# riscurino.net
KiCad netlist of a schematic drawn in EAGLE
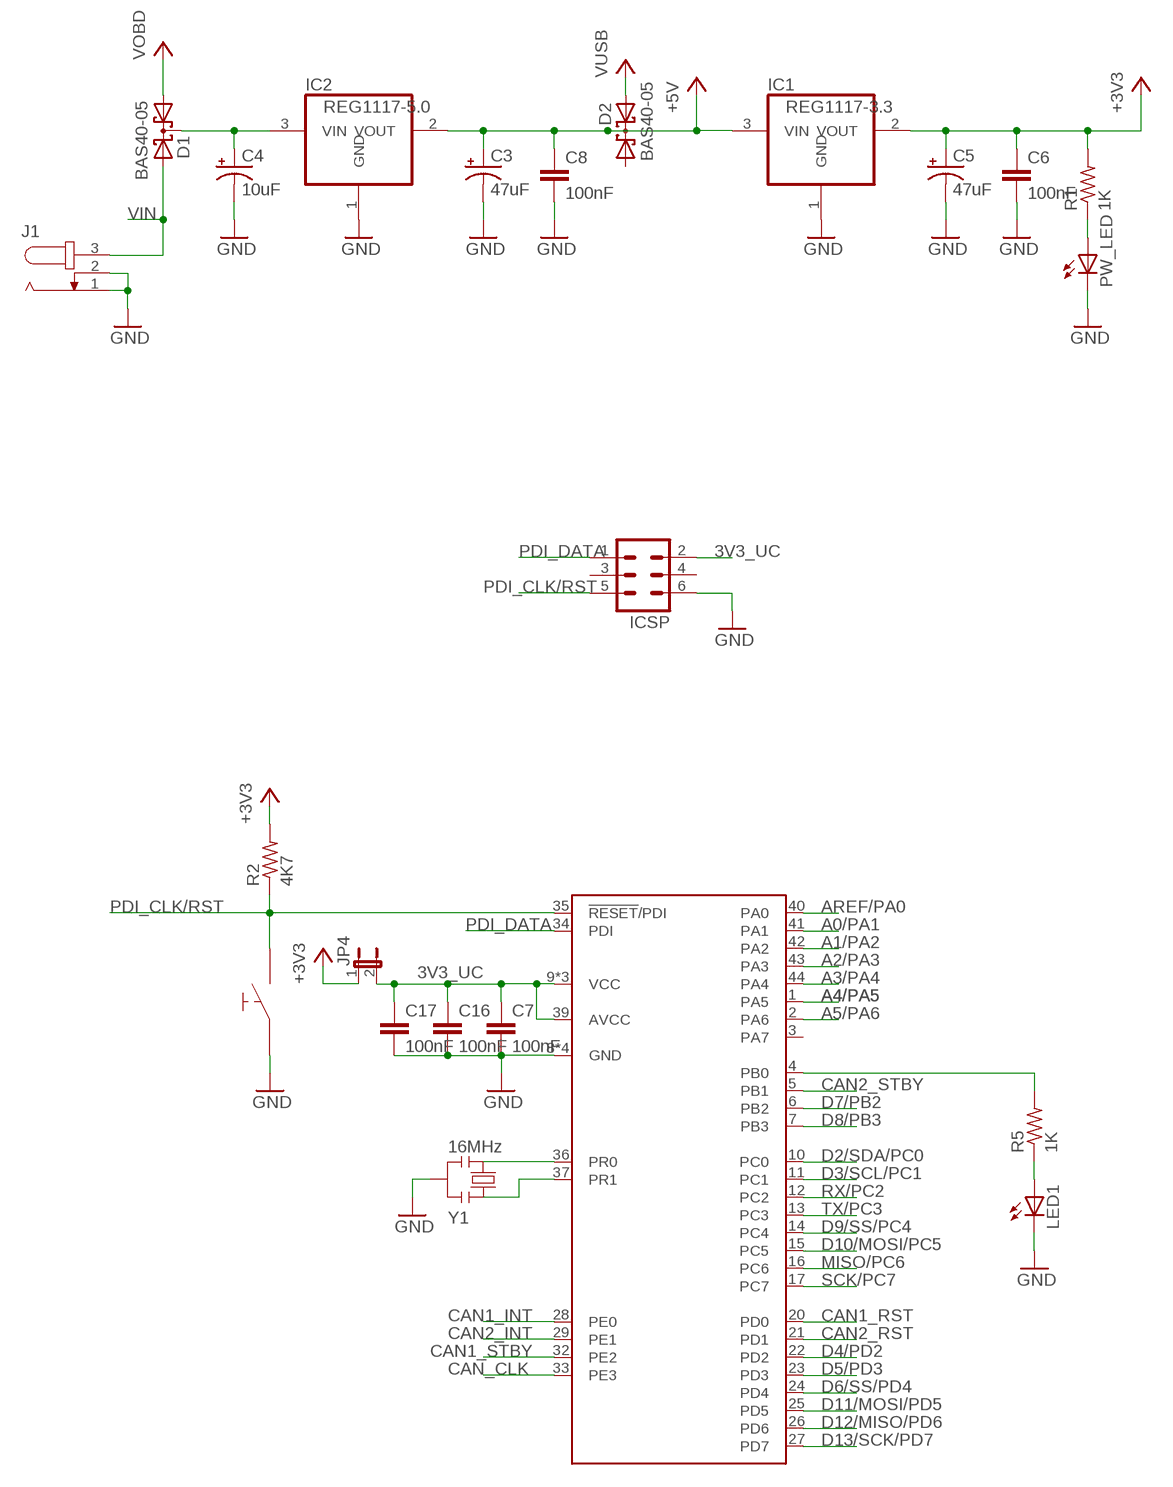
[diagram p0: schematic, sheet 1, part 1 of 2]
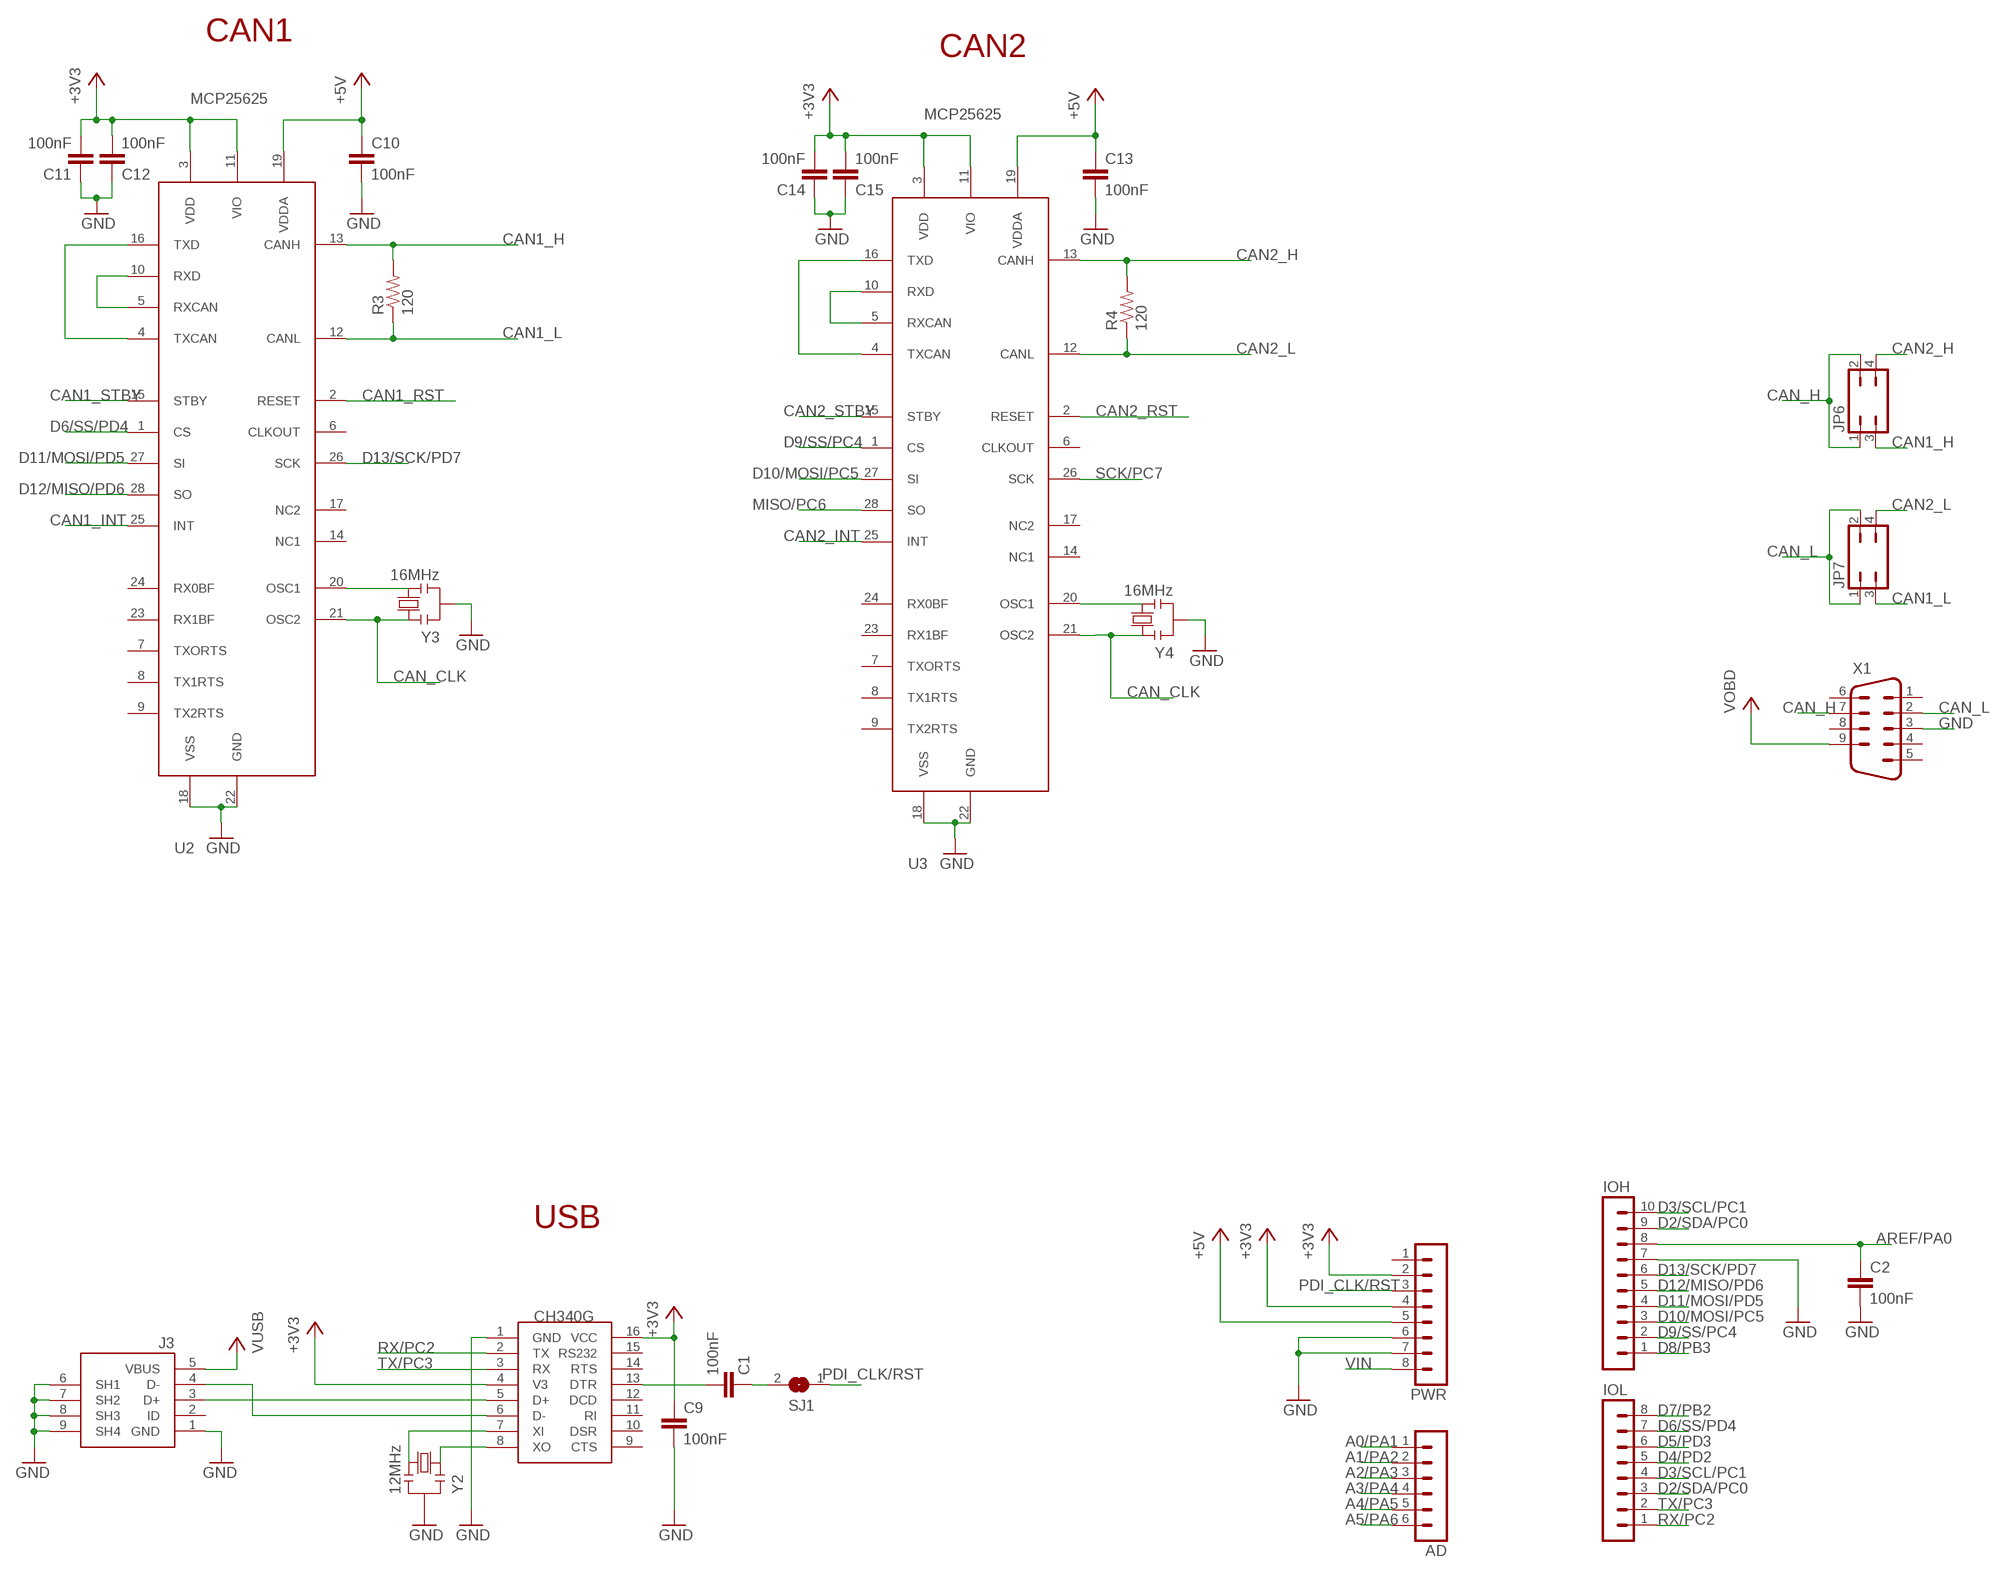
[diagram p1: schematic, sheet 1, part 2 of 2]

(export (version "E")
  (design (tool "Eeschema 10.0.6"))
  (components
    (comp (ref "AD")
      (value "MA06-1")
      (footprint "eagle-import:MA06-1")
      (libsource (lib "eagle-import") (part "MA06-1"))
    )
    (comp (ref "C1")
      (value "100nF")
      (footprint "eagle-import:C0805")
      (libsource (lib "eagle-import") (part "C-EUC0805"))
    )
    (comp (ref "C2")
      (value "100nF")
      (footprint "eagle-import:C0805")
      (libsource (lib "eagle-import") (part "C-EUC0805"))
    )
    (comp (ref "C3")
      (value "47uF")
      (footprint "eagle-import:PANASONIC_C")
      (libsource (lib "eagle-import") (part "CPOL-USC"))
    )
    (comp (ref "C4")
      (value "10uF")
      (footprint "eagle-import:PANASONIC_C")
      (libsource (lib "eagle-import") (part "CPOL-USC"))
    )
    (comp (ref "C5")
      (value "47uF")
      (footprint "eagle-import:PANASONIC_C")
      (libsource (lib "eagle-import") (part "CPOL-USC"))
    )
    (comp (ref "C6")
      (value "100nF")
      (footprint "eagle-import:C0805")
      (libsource (lib "eagle-import") (part "C-EUC0805"))
    )
    (comp (ref "C7")
      (value "100nF")
      (footprint "eagle-import:C0805")
      (libsource (lib "eagle-import") (part "C-EUC0805"))
    )
    (comp (ref "C8")
      (value "100nF")
      (footprint "eagle-import:C0805")
      (libsource (lib "eagle-import") (part "C-EUC0805"))
    )
    (comp (ref "C9")
      (value "100nF")
      (footprint "eagle-import:C0805")
      (libsource (lib "eagle-import") (part "C-EUC0805"))
    )
    (comp (ref "C10")
      (value "100nF")
      (footprint "eagle-import:C0805")
      (libsource (lib "eagle-import") (part "C-EUC0805"))
    )
    (comp (ref "C11")
      (value "100nF")
      (footprint "eagle-import:C0805")
      (libsource (lib "eagle-import") (part "C-EUC0805"))
    )
    (comp (ref "C12")
      (value "100nF")
      (footprint "eagle-import:C0805")
      (libsource (lib "eagle-import") (part "C-EUC0805"))
    )
    (comp (ref "C13")
      (value "100nF")
      (footprint "eagle-import:C0805")
      (libsource (lib "eagle-import") (part "C-EUC0805"))
    )
    (comp (ref "C14")
      (value "100nF")
      (footprint "eagle-import:C0805")
      (libsource (lib "eagle-import") (part "C-EUC0805"))
    )
    (comp (ref "C15")
      (value "100nF")
      (footprint "eagle-import:C0805")
      (libsource (lib "eagle-import") (part "C-EUC0805"))
    )
    (comp (ref "C16")
      (value "100nF")
      (footprint "eagle-import:C0805")
      (libsource (lib "eagle-import") (part "C-EUC0805"))
    )
    (comp (ref "C17")
      (value "100nF")
      (footprint "eagle-import:C0805")
      (libsource (lib "eagle-import") (part "C-EUC0805"))
    )
    (comp (ref "D1")
      (value "BAS40-05")
      (footprint "eagle-import:SOT23")
      (libsource (lib "eagle-import") (part "BAS40-05"))
    )
    (comp (ref "D2")
      (value "BAS40-05")
      (footprint "eagle-import:SOT23")
      (libsource (lib "eagle-import") (part "BAS40-05"))
    )
    (comp (ref "IC1")
      (value "REG1117-3.3")
      (footprint "eagle-import:SOT223")
      (fields (field (name "MPN") "REG1117"))
      (libsource (lib "eagle-import") (part "REG1117"))
    )
    (comp (ref "IC2")
      (value "REG1117-5.0")
      (footprint "eagle-import:SOT223")
      (fields (field (name "MPN") "REG1117"))
      (libsource (lib "eagle-import") (part "REG1117"))
    )
    (comp (ref "ICSP")
      (value "MA03-2")
      (footprint "eagle-import:MA03-2")
      (libsource (lib "eagle-import") (part "MA03-2"))
    )
    (comp (ref "IOH")
      (value "MA10-1")
      (footprint "eagle-import:MA10-1")
      (libsource (lib "eagle-import") (part "MA10-1"))
    )
    (comp (ref "IOL")
      (value "MA08-1")
      (footprint "eagle-import:MA08-1")
      (libsource (lib "eagle-import") (part "MA08-1"))
    )
    (comp (ref "J1")
      (value "JACK-PLUG0")
      (footprint "eagle-import:SPC4077")
      (libsource (lib "eagle-import") (part "JACK-PLUG0"))
    )
    (comp (ref "J3")
      (value "0219_14850")
      (footprint "eagle-import:USB-MINI-B_2")
      (fields (field (name "PART_NUMBER") "14850"))
      (libsource (lib "eagle-import") (part "0219_14850"))
    )
    (comp (ref "JP4")
      (value "JP1E")
      (footprint "eagle-import:JP1")
      (libsource (lib "eagle-import") (part "JP1E"))
    )
    (comp (ref "JP6")
      (value "JP2Q")
      (footprint "eagle-import:JP2Q")
      (libsource (lib "eagle-import") (part "JP2Q"))
    )
    (comp (ref "JP7")
      (value "JP2Q")
      (footprint "eagle-import:JP2Q")
      (libsource (lib "eagle-import") (part "JP2Q"))
    )
    (comp (ref "LED1")
      (value "LEDCHIPLED_0805")
      (footprint "eagle-import:CHIPLED_0805")
      (libsource (lib "eagle-import") (part "LEDCHIPLED_0805"))
    )
    (comp (ref "PWR")
      (value "MA08-1")
      (footprint "eagle-import:MA08-1")
      (libsource (lib "eagle-import") (part "MA08-1"))
    )
    (comp (ref "PW_LED")
      (value "LEDCHIPLED_0805")
      (footprint "eagle-import:CHIPLED_0805")
      (libsource (lib "eagle-import") (part "LEDCHIPLED_0805"))
    )
    (comp (ref "R1")
      (value "1K")
      (footprint "eagle-import:R0805")
      (libsource (lib "eagle-import") (part "R-US_R0805"))
    )
    (comp (ref "R2")
      (value "4K7")
      (footprint "eagle-import:R0805")
      (libsource (lib "eagle-import") (part "R-US_R0805"))
    )
    (comp (ref "R3")
      (value "120")
      (footprint "eagle-import:R0805")
      (libsource (lib "eagle-import") (part "R-US_R0805"))
    )
    (comp (ref "R4")
      (value "120")
      (footprint "eagle-import:R0805")
      (libsource (lib "eagle-import") (part "R-US_R0805"))
    )
    (comp (ref "R5")
      (value "1K")
      (footprint "eagle-import:R0805")
      (libsource (lib "eagle-import") (part "R-US_R0805"))
    )
    (comp (ref "SJ1") (value "SJ") (footprint "eagle-import:SJ") (libsource (lib "eagle-import") (part "SJ")))
    (comp (ref "U$1")
      (value "SWITCH_3X6")
      (footprint "eagle-import:SWITCH_3X6")
      (libsource (lib "eagle-import") (part "SWITCH_3X6"))
    )
    (comp (ref "U1")
      (value "ATXMEGA128A4U-AU")
      (footprint "eagle-import:TQFP-44A-44")
      (libsource (lib "eagle-import") (part "ATXMEGA128A4U-AU"))
    )
    (comp (ref "U2")
      (value "MCP25625")
      (footprint "eagle-import:QFN28")
      (libsource (lib "eagle-import") (part "MCP25625"))
    )
    (comp (ref "U3")
      (value "MCP25625")
      (footprint "eagle-import:QFN28")
      (libsource (lib "eagle-import") (part "MCP25625"))
    )
    (comp (ref "U4")
      (value "CH340G")
      (footprint "eagle-import:SOIC16")
      (libsource (lib "eagle-import") (part "CH340G"))
    )
    (comp (ref "X1")
      (value "M09HP")
      (footprint "eagle-import:M09HP")
      (libsource (lib "eagle-import") (part "M09HP"))
    )
    (comp (ref "Y1")
      (value "16MHz")
      (footprint "eagle-import:RESONATOR")
      (fields (field (name "PART_NUMBER") "CSTCE16M0V53-R0"))
      (libsource (lib "eagle-import") (part "0011_CSTCE16M0V53-R0"))
    )
    (comp (ref "Y2")
      (value "12MHz")
      (footprint "eagle-import:RESONATOR")
      (fields (field (name "PART_NUMBER") "CSTCE16M0V53-R0"))
      (libsource (lib "eagle-import") (part "0011_CSTCE16M0V53-R0"))
    )
    (comp (ref "Y3")
      (value "16MHz")
      (footprint "eagle-import:RESONATOR")
      (fields (field (name "PART_NUMBER") "CSTCE16M0V53-R0"))
      (libsource (lib "eagle-import") (part "0011_CSTCE16M0V53-R0"))
    )
    (comp (ref "Y4")
      (value "16MHz")
      (footprint "eagle-import:RESONATOR")
      (fields (field (name "PART_NUMBER") "CSTCE16M0V53-R0"))
      (libsource (lib "eagle-import") (part "0011_CSTCE16M0V53-R0"))
    )
  )
  (nets
    (net (code "1") (name "+3V3") (class "Default")
      (node (ref "C11") (pin "2") (pinfunction "2_2") (pintype "passive"))
      (node (ref "C12") (pin "2") (pinfunction "2_2") (pintype "passive"))
      (node (ref "C14") (pin "2") (pinfunction "2_2") (pintype "passive"))
      (node (ref "C15") (pin "2") (pinfunction "2_2") (pintype "passive"))
      (node (ref "C5") (pin "+") (pinfunction "+_+") (pintype "passive"))
      (node (ref "C6") (pin "1") (pinfunction "1_1") (pintype "passive"))
      (node (ref "C9") (pin "1") (pinfunction "1_1") (pintype "passive"))
      (node (ref "IC1") (pin "2") (pinfunction "VOUT_2") (pintype "output"))
      (node (ref "JP4") (pin "1") (pinfunction "1_1") (pintype "passive"))
      (node (ref "PWR") (pin "2") (pinfunction "2_2") (pintype "passive"))
      (node (ref "PWR") (pin "4") (pinfunction "4_4") (pintype "passive"))
      (node (ref "R1") (pin "2") (pinfunction "2_2") (pintype "passive"))
      (node (ref "R2") (pin "2") (pinfunction "2_2") (pintype "passive"))
      (node (ref "U2") (pin "11") (pinfunction "VIO_11") (pintype "bidirectional"))
      (node (ref "U2") (pin "3") (pinfunction "VDD_3") (pintype "power_in"))
      (node (ref "U3") (pin "11") (pinfunction "VIO_11") (pintype "bidirectional"))
      (node (ref "U3") (pin "3") (pinfunction "VDD_3") (pintype "power_in"))
      (node (ref "U4") (pin "16") (pinfunction "VCC_16") (pintype "bidirectional"))
      (node (ref "U4") (pin "4") (pinfunction "V3_4") (pintype "bidirectional"))
    )
    (net (code "2") (name "+5V") (class "Default")
      (node (ref "C10") (pin "1") (pinfunction "1_1") (pintype "passive"))
      (node (ref "C13") (pin "1") (pinfunction "1_1") (pintype "passive"))
      (node (ref "C3") (pin "+") (pinfunction "+_+") (pintype "passive"))
      (node (ref "C8") (pin "1") (pinfunction "1_1") (pintype "passive"))
      (node (ref "D2") (pin "3") (pinfunction "C_3") (pintype "passive"))
      (node (ref "IC1") (pin "3") (pinfunction "VIN_3") (pintype "input"))
      (node (ref "IC2") (pin "2") (pinfunction "VOUT_2") (pintype "output"))
      (node (ref "PWR") (pin "5") (pinfunction "5_5") (pintype "passive"))
      (node (ref "U2") (pin "19") (pinfunction "VDDA_19") (pintype "power_in"))
      (node (ref "U3") (pin "19") (pinfunction "VDDA_19") (pintype "power_in"))
    )
    (net (code "3") (name "/3V3_UC") (class "Default")
      (node (ref "C16") (pin "1") (pinfunction "1_1") (pintype "passive"))
      (node (ref "C17") (pin "1") (pinfunction "1_1") (pintype "passive"))
      (node (ref "C7") (pin "1") (pinfunction "1_1") (pintype "passive"))
      (node (ref "ICSP") (pin "2") (pinfunction "2_2") (pintype "passive"))
      (node (ref "JP4") (pin "2") (pinfunction "2_2") (pintype "passive"))
      (node (ref "U1") (pin "19") (pinfunction "VCC_19") (pintype "power_in"))
      (node (ref "U1") (pin "31") (pinfunction "VCC_31") (pintype "power_in"))
      (node (ref "U1") (pin "39") (pinfunction "AVCC_39") (pintype "power_in"))
      (node (ref "U1") (pin "9") (pinfunction "VCC_9") (pintype "power_in"))
    )
    (net (code "4") (name "/A0{slash}PA1") (class "Default")
      (node (ref "AD") (pin "1") (pinfunction "1_1") (pintype "passive"))
      (node (ref "U1") (pin "41") (pinfunction "PA1_41") (pintype "bidirectional"))
    )
    (net (code "5") (name "/A1{slash}PA2") (class "Default")
      (node (ref "AD") (pin "2") (pinfunction "2_2") (pintype "passive"))
      (node (ref "U1") (pin "42") (pinfunction "PA2_42") (pintype "bidirectional"))
    )
    (net (code "6") (name "/A2{slash}PA3") (class "Default")
      (node (ref "AD") (pin "3") (pinfunction "3_3") (pintype "passive"))
      (node (ref "U1") (pin "43") (pinfunction "PA3_43") (pintype "bidirectional"))
    )
    (net (code "7") (name "/A3{slash}PA4") (class "Default")
      (node (ref "AD") (pin "4") (pinfunction "4_4") (pintype "passive"))
      (node (ref "U1") (pin "44") (pinfunction "PA4_44") (pintype "bidirectional"))
    )
    (net (code "8") (name "/A4{slash}PA5") (class "Default")
      (node (ref "AD") (pin "5") (pinfunction "5_5") (pintype "passive"))
      (node (ref "U1") (pin "1") (pinfunction "PA5_1") (pintype "bidirectional"))
    )
    (net (code "9") (name "/A5{slash}PA6") (class "Default")
      (node (ref "AD") (pin "6") (pinfunction "6_6") (pintype "passive"))
      (node (ref "U1") (pin "2") (pinfunction "PA6_2") (pintype "bidirectional"))
    )
    (net (code "10") (name "/AREF{slash}PA0") (class "Default")
      (node (ref "C2") (pin "1") (pinfunction "1_1") (pintype "passive"))
      (node (ref "IOH") (pin "8") (pinfunction "8_8") (pintype "passive"))
      (node (ref "U1") (pin "40") (pinfunction "PA0_40") (pintype "bidirectional"))
    )
    (net (code "11") (name "/CAN1_H") (class "Default")
      (node (ref "JP6") (pin "3") (pinfunction "3_3") (pintype "passive"))
      (node (ref "R3") (pin "2") (pinfunction "2_2") (pintype "passive"))
      (node (ref "U2") (pin "13") (pinfunction "CANH_13") (pintype "bidirectional"))
    )
    (net (code "12") (name "/CAN1_INT") (class "Default")
      (node (ref "U1") (pin "28") (pinfunction "PE0_28") (pintype "bidirectional"))
      (node (ref "U2") (pin "25") (pinfunction "INT_25") (pintype "bidirectional"))
    )
    (net (code "13") (name "/CAN1_L") (class "Default")
      (node (ref "JP7") (pin "3") (pinfunction "3_3") (pintype "passive"))
      (node (ref "R3") (pin "1") (pinfunction "1_1") (pintype "passive"))
      (node (ref "U2") (pin "12") (pinfunction "CANL_12") (pintype "bidirectional"))
    )
    (net (code "14") (name "/CAN1_RST") (class "Default")
      (node (ref "U1") (pin "20") (pinfunction "PD0_20") (pintype "bidirectional"))
      (node (ref "U2") (pin "2") (pinfunction "RESET_2") (pintype "bidirectional"))
    )
    (net (code "15") (name "/CAN1_STBY") (class "Default")
      (node (ref "U1") (pin "32") (pinfunction "PE2_32") (pintype "bidirectional"))
      (node (ref "U2") (pin "15") (pinfunction "STBY_15") (pintype "bidirectional"))
    )
    (net (code "16") (name "/CAN2_H") (class "Default")
      (node (ref "JP6") (pin "4") (pinfunction "4_4") (pintype "passive"))
      (node (ref "R4") (pin "2") (pinfunction "2_2") (pintype "passive"))
      (node (ref "U3") (pin "13") (pinfunction "CANH_13") (pintype "bidirectional"))
    )
    (net (code "17") (name "/CAN2_INT") (class "Default")
      (node (ref "U1") (pin "29") (pinfunction "PE1_29") (pintype "bidirectional"))
      (node (ref "U3") (pin "25") (pinfunction "INT_25") (pintype "bidirectional"))
    )
    (net (code "18") (name "/CAN2_L") (class "Default")
      (node (ref "JP7") (pin "4") (pinfunction "4_4") (pintype "passive"))
      (node (ref "R4") (pin "1") (pinfunction "1_1") (pintype "passive"))
      (node (ref "U3") (pin "12") (pinfunction "CANL_12") (pintype "bidirectional"))
    )
    (net (code "19") (name "/CAN2_RST") (class "Default")
      (node (ref "U1") (pin "21") (pinfunction "PD1_21") (pintype "bidirectional"))
      (node (ref "U3") (pin "2") (pinfunction "RESET_2") (pintype "bidirectional"))
    )
    (net (code "20") (name "/CAN2_STBY") (class "Default")
      (node (ref "U1") (pin "5") (pinfunction "PB1_5") (pintype "bidirectional"))
      (node (ref "U3") (pin "15") (pinfunction "STBY_15") (pintype "bidirectional"))
    )
    (net (code "21") (name "/CAN_CLK") (class "Default")
      (node (ref "U1") (pin "33") (pinfunction "PE3_33") (pintype "bidirectional"))
      (node (ref "U2") (pin "21") (pinfunction "OSC2_21") (pintype "bidirectional"))
      (node (ref "U3") (pin "21") (pinfunction "OSC2_21") (pintype "bidirectional"))
      (node (ref "Y3") (pin "1") (pinfunction "1_1") (pintype "passive"))
      (node (ref "Y4") (pin "1") (pinfunction "1_1") (pintype "passive"))
    )
    (net (code "22") (name "/CAN_H") (class "Default")
      (node (ref "JP6") (pin "1") (pinfunction "1_1") (pintype "passive"))
      (node (ref "JP6") (pin "2") (pinfunction "2_2") (pintype "passive"))
      (node (ref "X1") (pin "7") (pinfunction "7_7") (pintype "passive"))
    )
    (net (code "23") (name "/CAN_L") (class "Default")
      (node (ref "JP7") (pin "1") (pinfunction "1_1") (pintype "passive"))
      (node (ref "JP7") (pin "2") (pinfunction "2_2") (pintype "passive"))
      (node (ref "X1") (pin "2") (pinfunction "2_2") (pintype "passive"))
    )
    (net (code "24") (name "/D2{slash}SDA{slash}PC0") (class "Default")
      (node (ref "IOH") (pin "9") (pinfunction "9_9") (pintype "passive"))
      (node (ref "IOL") (pin "3") (pinfunction "3_3") (pintype "passive"))
      (node (ref "U1") (pin "10") (pinfunction "PC0_10") (pintype "bidirectional"))
    )
    (net (code "25") (name "/D3{slash}SCL{slash}PC1") (class "Default")
      (node (ref "IOH") (pin "10") (pinfunction "10_10") (pintype "passive"))
      (node (ref "IOL") (pin "4") (pinfunction "4_4") (pintype "passive"))
      (node (ref "U1") (pin "11") (pinfunction "PC1_11") (pintype "bidirectional"))
    )
    (net (code "26") (name "/D4{slash}PD2") (class "Default")
      (node (ref "IOL") (pin "5") (pinfunction "5_5") (pintype "passive"))
      (node (ref "U1") (pin "22") (pinfunction "PD2_22") (pintype "bidirectional"))
    )
    (net (code "27") (name "/D5{slash}PD3") (class "Default")
      (node (ref "IOL") (pin "6") (pinfunction "6_6") (pintype "passive"))
      (node (ref "U1") (pin "23") (pinfunction "PD3_23") (pintype "bidirectional"))
    )
    (net (code "28") (name "/D6{slash}SS{slash}PD4") (class "Default")
      (node (ref "IOL") (pin "7") (pinfunction "7_7") (pintype "passive"))
      (node (ref "U1") (pin "24") (pinfunction "PD4_24") (pintype "bidirectional"))
      (node (ref "U2") (pin "1") (pinfunction "CS_1") (pintype "bidirectional"))
    )
    (net (code "29") (name "/D7{slash}PB2") (class "Default")
      (node (ref "IOL") (pin "8") (pinfunction "8_8") (pintype "passive"))
      (node (ref "U1") (pin "6") (pinfunction "PB2_6") (pintype "bidirectional"))
    )
    (net (code "30") (name "/D8{slash}PB3") (class "Default")
      (node (ref "IOH") (pin "1") (pinfunction "1_1") (pintype "passive"))
      (node (ref "U1") (pin "7") (pinfunction "PB3_7") (pintype "bidirectional"))
    )
    (net (code "31") (name "/D9{slash}SS{slash}PC4") (class "Default")
      (node (ref "IOH") (pin "2") (pinfunction "2_2") (pintype "passive"))
      (node (ref "U1") (pin "14") (pinfunction "PC4_14") (pintype "bidirectional"))
      (node (ref "U3") (pin "1") (pinfunction "CS_1") (pintype "bidirectional"))
    )
    (net (code "32") (name "/D10{slash}MOSI{slash}PC5") (class "Default")
      (node (ref "IOH") (pin "3") (pinfunction "3_3") (pintype "passive"))
      (node (ref "U1") (pin "15") (pinfunction "PC5_15") (pintype "bidirectional"))
      (node (ref "U3") (pin "27") (pinfunction "SI_27") (pintype "bidirectional"))
    )
    (net (code "33") (name "/D11{slash}MOSI{slash}PD5") (class "Default")
      (node (ref "IOH") (pin "4") (pinfunction "4_4") (pintype "passive"))
      (node (ref "U1") (pin "25") (pinfunction "PD5_25") (pintype "bidirectional"))
      (node (ref "U2") (pin "27") (pinfunction "SI_27") (pintype "bidirectional"))
    )
    (net (code "34") (name "/D12{slash}MISO{slash}PD6") (class "Default")
      (node (ref "IOH") (pin "5") (pinfunction "5_5") (pintype "passive"))
      (node (ref "U1") (pin "26") (pinfunction "PD6_26") (pintype "bidirectional"))
      (node (ref "U2") (pin "28") (pinfunction "SO_28") (pintype "bidirectional"))
    )
    (net (code "35") (name "/D13{slash}SCK{slash}PD7") (class "Default")
      (node (ref "IOH") (pin "6") (pinfunction "6_6") (pintype "passive"))
      (node (ref "U1") (pin "27") (pinfunction "PD7_27") (pintype "bidirectional"))
      (node (ref "U2") (pin "26") (pinfunction "SCK_26") (pintype "bidirectional"))
    )
    (net (code "36") (name "/MISO{slash}PC6") (class "Default")
      (node (ref "U1") (pin "16") (pinfunction "PC6_16") (pintype "bidirectional"))
      (node (ref "U3") (pin "28") (pinfunction "SO_28") (pintype "bidirectional"))
    )
    (net (code "37") (name "/PDI_CLK{slash}RST") (class "Default")
      (node (ref "ICSP") (pin "5") (pinfunction "5_5") (pintype "passive"))
      (node (ref "PWR") (pin "3") (pinfunction "3_3") (pintype "passive"))
      (node (ref "R2") (pin "1") (pinfunction "1_1") (pintype "passive"))
      (node (ref "SJ1") (pin "1") (pinfunction "1_1") (pintype "passive"))
      (node (ref "U$1") (pin "P$2") (pinfunction "P$2_P$2") (pintype "bidirectional"))
      (node (ref "U1") (pin "35") (pinfunction "~{RESET}/PDI_35") (pintype "bidirectional"))
    )
    (net (code "38") (name "/PDI_DATA") (class "Default")
      (node (ref "ICSP") (pin "1") (pinfunction "1_1") (pintype "passive"))
      (node (ref "U1") (pin "34") (pinfunction "PDI_34") (pintype "bidirectional"))
    )
    (net (code "39") (name "/RX{slash}PC2") (class "Default")
      (node (ref "IOL") (pin "1") (pinfunction "1_1") (pintype "passive"))
      (node (ref "U1") (pin "12") (pinfunction "PC2_12") (pintype "bidirectional"))
      (node (ref "U4") (pin "2") (pinfunction "TX_2") (pintype "bidirectional"))
    )
    (net (code "40") (name "/SCK{slash}PC7") (class "Default")
      (node (ref "U1") (pin "17") (pinfunction "PC7_17") (pintype "bidirectional"))
      (node (ref "U3") (pin "26") (pinfunction "SCK_26") (pintype "bidirectional"))
    )
    (net (code "41") (name "/TX{slash}PC3") (class "Default")
      (node (ref "IOL") (pin "2") (pinfunction "2_2") (pintype "passive"))
      (node (ref "U1") (pin "13") (pinfunction "PC3_13") (pintype "bidirectional"))
      (node (ref "U4") (pin "3") (pinfunction "RX_3") (pintype "bidirectional"))
    )
    (net (code "42") (name "/VIN") (class "Default")
      (node (ref "D1") (pin "2") (pinfunction "A2_2") (pintype "passive"))
      (node (ref "J1") (pin "3") (pinfunction "3_3") (pintype "passive"))
      (node (ref "PWR") (pin "8") (pinfunction "8_8") (pintype "passive"))
    )
    (net (code "43") (name "GND") (class "Default")
      (node (ref "C10") (pin "2") (pinfunction "2_2") (pintype "passive"))
      (node (ref "C11") (pin "1") (pinfunction "1_1") (pintype "passive"))
      (node (ref "C12") (pin "1") (pinfunction "1_1") (pintype "passive"))
      (node (ref "C13") (pin "2") (pinfunction "2_2") (pintype "passive"))
      (node (ref "C14") (pin "1") (pinfunction "1_1") (pintype "passive"))
      (node (ref "C15") (pin "1") (pinfunction "1_1") (pintype "passive"))
      (node (ref "C16") (pin "2") (pinfunction "2_2") (pintype "passive"))
      (node (ref "C17") (pin "2") (pinfunction "2_2") (pintype "passive"))
      (node (ref "C2") (pin "2") (pinfunction "2_2") (pintype "passive"))
      (node (ref "C3") (pin "-") (pinfunction "-_-") (pintype "passive"))
      (node (ref "C4") (pin "-") (pinfunction "-_-") (pintype "passive"))
      (node (ref "C5") (pin "-") (pinfunction "-_-") (pintype "passive"))
      (node (ref "C6") (pin "2") (pinfunction "2_2") (pintype "passive"))
      (node (ref "C7") (pin "2") (pinfunction "2_2") (pintype "passive"))
      (node (ref "C8") (pin "2") (pinfunction "2_2") (pintype "passive"))
      (node (ref "C9") (pin "2") (pinfunction "2_2") (pintype "passive"))
      (node (ref "IC1") (pin "1") (pinfunction "GND_1") (pintype "power_in"))
      (node (ref "IC2") (pin "1") (pinfunction "GND_1") (pintype "power_in"))
      (node (ref "ICSP") (pin "6") (pinfunction "6_6") (pintype "passive"))
      (node (ref "IOH") (pin "7") (pinfunction "7_7") (pintype "passive"))
      (node (ref "J1") (pin "1") (pinfunction "1_1") (pintype "passive"))
      (node (ref "J1") (pin "2") (pinfunction "2_2") (pintype "passive"))
      (node (ref "J3") (pin "1") (pinfunction "GND_1") (pintype "passive"))
      (node (ref "J3") (pin "6") (pinfunction "SH1_6") (pintype "passive"))
      (node (ref "J3") (pin "7") (pinfunction "SH2_7") (pintype "passive"))
      (node (ref "J3") (pin "8") (pinfunction "SH3_8") (pintype "passive"))
      (node (ref "J3") (pin "9") (pinfunction "SH4_9") (pintype "passive"))
      (node (ref "LED1") (pin "C") (pinfunction "C_C") (pintype "passive"))
      (node (ref "PWR") (pin "6") (pinfunction "6_6") (pintype "passive"))
      (node (ref "PWR") (pin "7") (pinfunction "7_7") (pintype "passive"))
      (node (ref "PW_LED") (pin "C") (pinfunction "C_C") (pintype "passive"))
      (node (ref "U$1") (pin "P$1") (pinfunction "P$1_P$1") (pintype "bidirectional"))
      (node (ref "U1") (pin "18") (pinfunction "GND_18") (pintype "power_in"))
      (node (ref "U1") (pin "30") (pinfunction "GND_30") (pintype "power_in"))
      (node (ref "U1") (pin "38") (pinfunction "GND_38") (pintype "power_in"))
      (node (ref "U1") (pin "8") (pinfunction "GND_8") (pintype "power_in"))
      (node (ref "U2") (pin "18") (pinfunction "VSS_18") (pintype "power_in"))
      (node (ref "U2") (pin "22") (pinfunction "GND_22") (pintype "power_in"))
      (node (ref "U3") (pin "18") (pinfunction "VSS_18") (pintype "power_in"))
      (node (ref "U3") (pin "22") (pinfunction "GND_22") (pintype "power_in"))
      (node (ref "U4") (pin "1") (pinfunction "GND_1") (pintype "bidirectional"))
      (node (ref "X1") (pin "3") (pinfunction "3_3") (pintype "passive"))
      (node (ref "Y1") (pin "2") (pinfunction "2_2") (pintype "passive"))
      (node (ref "Y2") (pin "2") (pinfunction "2_2") (pintype "passive"))
      (node (ref "Y3") (pin "2") (pinfunction "2_2") (pintype "passive"))
      (node (ref "Y4") (pin "2") (pinfunction "2_2") (pintype "passive"))
    )
    (net (code "44") (name "Net-(C1-Pad1)") (class "Default")
      (node (ref "C1") (pin "1") (pinfunction "1_1") (pintype "passive"))
      (node (ref "SJ1") (pin "2") (pinfunction "2_2") (pintype "passive"))
    )
    (net (code "45") (name "Net-(D1-C)") (class "Default")
      (node (ref "C4") (pin "+") (pinfunction "+_+") (pintype "passive"))
      (node (ref "D1") (pin "3") (pinfunction "C_3") (pintype "passive"))
      (node (ref "IC2") (pin "3") (pinfunction "VIN_3") (pintype "input"))
    )
    (net (code "46") (name "Net-(J3-D+)") (class "Default")
      (node (ref "J3") (pin "3") (pinfunction "D+_3") (pintype "bidirectional"))
      (node (ref "U4") (pin "5") (pinfunction "D+_5") (pintype "bidirectional"))
    )
    (net (code "47") (name "Net-(J3-D-)") (class "Default")
      (node (ref "J3") (pin "4") (pinfunction "D-_4") (pintype "bidirectional"))
      (node (ref "U4") (pin "6") (pinfunction "D-_6") (pintype "bidirectional"))
    )
    (net (code "48") (name "Net-(LED1-PadA)") (class "Default")
      (node (ref "LED1") (pin "A") (pinfunction "A_A") (pintype "passive"))
      (node (ref "R5") (pin "1") (pinfunction "1_1") (pintype "passive"))
    )
    (net (code "49") (name "Net-(PW_LED-PadA)") (class "Default")
      (node (ref "PW_LED") (pin "A") (pinfunction "A_A") (pintype "passive"))
      (node (ref "R1") (pin "1") (pinfunction "1_1") (pintype "passive"))
    )
    (net (code "50") (name "Net-(U1-PB0)") (class "Default")
      (node (ref "R5") (pin "2") (pinfunction "2_2") (pintype "passive"))
      (node (ref "U1") (pin "4") (pinfunction "PB0_4") (pintype "bidirectional"))
    )
    (net (code "51") (name "Net-(U1-PR0)") (class "Default")
      (node (ref "U1") (pin "36") (pinfunction "PR0_36") (pintype "bidirectional"))
      (node (ref "Y1") (pin "3") (pinfunction "3_3") (pintype "passive"))
    )
    (net (code "52") (name "Net-(U1-PR1)") (class "Default")
      (node (ref "U1") (pin "37") (pinfunction "PR1_37") (pintype "bidirectional"))
      (node (ref "Y1") (pin "1") (pinfunction "1_1") (pintype "passive"))
    )
    (net (code "53") (name "Net-(U2-OSC1)") (class "Default")
      (node (ref "U2") (pin "20") (pinfunction "OSC1_20") (pintype "bidirectional"))
      (node (ref "Y3") (pin "3") (pinfunction "3_3") (pintype "passive"))
    )
    (net (code "54") (name "Net-(U2-RXCAN)") (class "Default")
      (node (ref "U2") (pin "10") (pinfunction "RXD_10") (pintype "bidirectional"))
      (node (ref "U2") (pin "5") (pinfunction "RXCAN_5") (pintype "bidirectional"))
    )
    (net (code "55") (name "Net-(U2-TXCAN)") (class "Default")
      (node (ref "U2") (pin "16") (pinfunction "TXD_16") (pintype "bidirectional"))
      (node (ref "U2") (pin "4") (pinfunction "TXCAN_4") (pintype "bidirectional"))
    )
    (net (code "56") (name "Net-(U3-OSC1)") (class "Default")
      (node (ref "U3") (pin "20") (pinfunction "OSC1_20") (pintype "bidirectional"))
      (node (ref "Y4") (pin "3") (pinfunction "3_3") (pintype "passive"))
    )
    (net (code "57") (name "Net-(U3-RXCAN)") (class "Default")
      (node (ref "U3") (pin "10") (pinfunction "RXD_10") (pintype "bidirectional"))
      (node (ref "U3") (pin "5") (pinfunction "RXCAN_5") (pintype "bidirectional"))
    )
    (net (code "58") (name "Net-(U3-TXCAN)") (class "Default")
      (node (ref "U3") (pin "16") (pinfunction "TXD_16") (pintype "bidirectional"))
      (node (ref "U3") (pin "4") (pinfunction "TXCAN_4") (pintype "bidirectional"))
    )
    (net (code "59") (name "Net-(U4-DTR)") (class "Default")
      (node (ref "C1") (pin "2") (pinfunction "2_2") (pintype "passive"))
      (node (ref "U4") (pin "13") (pinfunction "DTR_13") (pintype "bidirectional"))
    )
    (net (code "60") (name "Net-(U4-XI)") (class "Default")
      (node (ref "U4") (pin "7") (pinfunction "XI_7") (pintype "bidirectional"))
      (node (ref "Y2") (pin "3") (pinfunction "3_3") (pintype "passive"))
    )
    (net (code "61") (name "Net-(U4-XO)") (class "Default")
      (node (ref "U4") (pin "8") (pinfunction "XO_8") (pintype "bidirectional"))
      (node (ref "Y2") (pin "1") (pinfunction "1_1") (pintype "passive"))
    )
    (net (code "62") (name "VOBD") (class "Default")
      (node (ref "D1") (pin "1") (pinfunction "A1_1") (pintype "passive"))
      (node (ref "X1") (pin "9") (pinfunction "9_9") (pintype "passive"))
    )
    (net (code "63") (name "VUSB") (class "Default")
      (node (ref "D2") (pin "2") (pinfunction "A2_2") (pintype "passive"))
      (node (ref "J3") (pin "5") (pinfunction "VBUS_5") (pintype "power_in"))
    )
    (net (code "64") (name "unconnected-(D2-A1-Pad1)") (class "Default")
      (node (ref "D2") (pin "1") (pinfunction "A1_1") (pintype "passive"))
    )
    (net (code "65") (name "unconnected-(ICSP-Pad3)") (class "Default")
      (node (ref "ICSP") (pin "3") (pinfunction "3_3") (pintype "passive"))
    )
    (net (code "66") (name "unconnected-(ICSP-Pad4)") (class "Default")
      (node (ref "ICSP") (pin "4") (pinfunction "4_4") (pintype "passive"))
    )
    (net (code "67") (name "unconnected-(J3-ID-Pad2)") (class "Default")
      (node (ref "J3") (pin "2") (pinfunction "ID_2") (pintype "bidirectional"))
    )
    (net (code "68") (name "unconnected-(PWR-Pad1)") (class "Default")
      (node (ref "PWR") (pin "1") (pinfunction "1_1") (pintype "passive"))
    )
    (net (code "69") (name "unconnected-(U1-PA7-Pad3)") (class "Default")
      (node (ref "U1") (pin "3") (pinfunction "PA7_3") (pintype "bidirectional"))
    )
    (net (code "70") (name "unconnected-(U2-CLKOUT-Pad6)") (class "Default")
      (node (ref "U2") (pin "6") (pinfunction "CLKOUT_6") (pintype "bidirectional"))
    )
    (net (code "71") (name "unconnected-(U2-NC1-Pad14)") (class "Default")
      (node (ref "U2") (pin "14") (pinfunction "NC1_14") (pintype "bidirectional"))
    )
    (net (code "72") (name "unconnected-(U2-NC2-Pad17)") (class "Default")
      (node (ref "U2") (pin "17") (pinfunction "NC2_17") (pintype "bidirectional"))
    )
    (net (code "73") (name "unconnected-(U2-RX0BF-Pad24)") (class "Default")
      (node (ref "U2") (pin "24") (pinfunction "RX0BF_24") (pintype "bidirectional"))
    )
    (net (code "74") (name "unconnected-(U2-RX1BF-Pad23)") (class "Default")
      (node (ref "U2") (pin "23") (pinfunction "RX1BF_23") (pintype "bidirectional"))
    )
    (net (code "75") (name "unconnected-(U2-TX1RTS-Pad8)") (class "Default")
      (node (ref "U2") (pin "8") (pinfunction "TX1RTS_8") (pintype "bidirectional"))
    )
    (net (code "76") (name "unconnected-(U2-TX2RTS-Pad9)") (class "Default")
      (node (ref "U2") (pin "9") (pinfunction "TX2RTS_9") (pintype "bidirectional"))
    )
    (net (code "77") (name "unconnected-(U2-TXORTS-Pad7)") (class "Default")
      (node (ref "U2") (pin "7") (pinfunction "TXORTS_7") (pintype "bidirectional"))
    )
    (net (code "78") (name "unconnected-(U3-CLKOUT-Pad6)") (class "Default")
      (node (ref "U3") (pin "6") (pinfunction "CLKOUT_6") (pintype "bidirectional"))
    )
    (net (code "79") (name "unconnected-(U3-NC1-Pad14)") (class "Default")
      (node (ref "U3") (pin "14") (pinfunction "NC1_14") (pintype "bidirectional"))
    )
    (net (code "80") (name "unconnected-(U3-NC2-Pad17)") (class "Default")
      (node (ref "U3") (pin "17") (pinfunction "NC2_17") (pintype "bidirectional"))
    )
    (net (code "81") (name "unconnected-(U3-RX0BF-Pad24)") (class "Default")
      (node (ref "U3") (pin "24") (pinfunction "RX0BF_24") (pintype "bidirectional"))
    )
    (net (code "82") (name "unconnected-(U3-RX1BF-Pad23)") (class "Default")
      (node (ref "U3") (pin "23") (pinfunction "RX1BF_23") (pintype "bidirectional"))
    )
    (net (code "83") (name "unconnected-(U3-TX1RTS-Pad8)") (class "Default")
      (node (ref "U3") (pin "8") (pinfunction "TX1RTS_8") (pintype "bidirectional"))
    )
    (net (code "84") (name "unconnected-(U3-TX2RTS-Pad9)") (class "Default")
      (node (ref "U3") (pin "9") (pinfunction "TX2RTS_9") (pintype "bidirectional"))
    )
    (net (code "85") (name "unconnected-(U3-TXORTS-Pad7)") (class "Default")
      (node (ref "U3") (pin "7") (pinfunction "TXORTS_7") (pintype "bidirectional"))
    )
    (net (code "86") (name "unconnected-(U4-CTS-Pad9)") (class "Default")
      (node (ref "U4") (pin "9") (pinfunction "CTS_9") (pintype "bidirectional"))
    )
    (net (code "87") (name "unconnected-(U4-DCD-Pad12)") (class "Default")
      (node (ref "U4") (pin "12") (pinfunction "DCD_12") (pintype "bidirectional"))
    )
    (net (code "88") (name "unconnected-(U4-DSR-Pad10)") (class "Default")
      (node (ref "U4") (pin "10") (pinfunction "DSR_10") (pintype "bidirectional"))
    )
    (net (code "89") (name "unconnected-(U4-RI-Pad11)") (class "Default")
      (node (ref "U4") (pin "11") (pinfunction "RI_11") (pintype "bidirectional"))
    )
    (net (code "90") (name "unconnected-(U4-RS232-Pad15)") (class "Default")
      (node (ref "U4") (pin "15") (pinfunction "RS232_15") (pintype "bidirectional"))
    )
    (net (code "91") (name "unconnected-(U4-RTS-Pad14)") (class "Default")
      (node (ref "U4") (pin "14") (pinfunction "RTS_14") (pintype "bidirectional"))
    )
    (net (code "92") (name "unconnected-(X1-Pad1)") (class "Default")
      (node (ref "X1") (pin "1") (pinfunction "1_1") (pintype "passive"))
    )
    (net (code "93") (name "unconnected-(X1-Pad4)") (class "Default")
      (node (ref "X1") (pin "4") (pinfunction "4_4") (pintype "passive"))
    )
    (net (code "94") (name "unconnected-(X1-Pad5)") (class "Default")
      (node (ref "X1") (pin "5") (pinfunction "5_5") (pintype "passive"))
    )
    (net (code "95") (name "unconnected-(X1-Pad6)") (class "Default")
      (node (ref "X1") (pin "6") (pinfunction "6_6") (pintype "passive"))
    )
    (net (code "96") (name "unconnected-(X1-Pad8)") (class "Default")
      (node (ref "X1") (pin "8") (pinfunction "8_8") (pintype "passive"))
    )
  )
)
